# MAX14870_Backend.net
KiCad netlist of a schematic drawn in Altium Designer
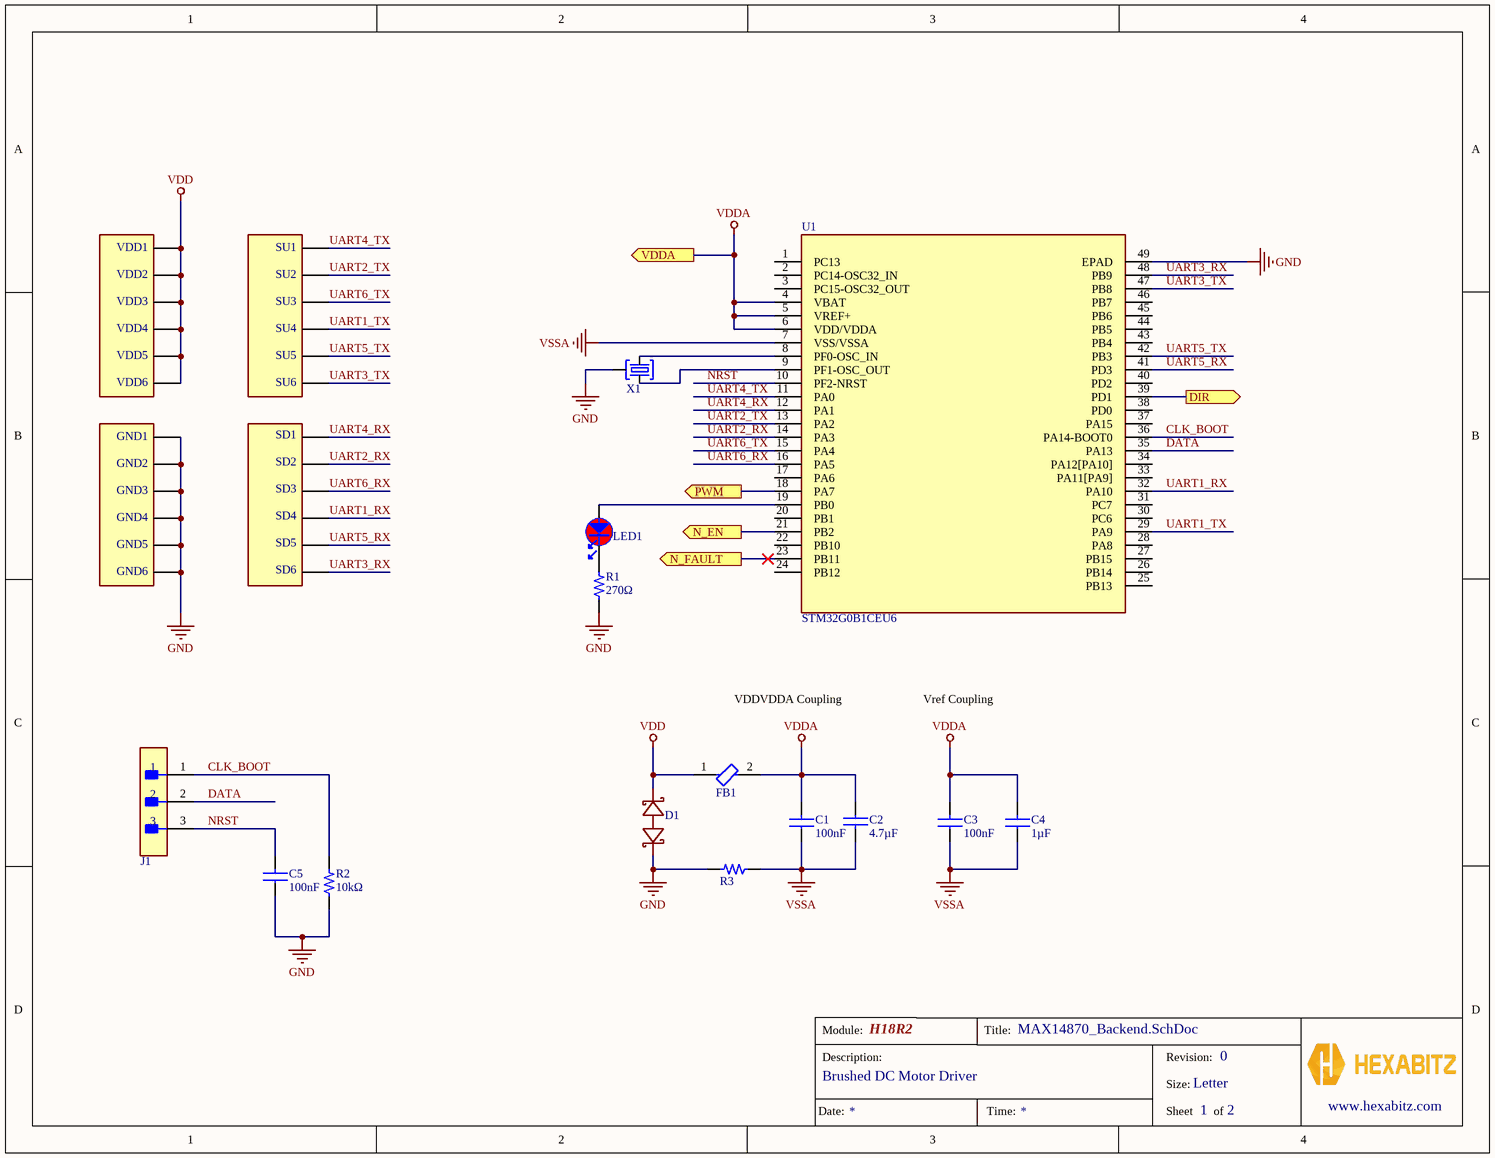
[diagram p0: MAX14870_Backend.SchDoc]

(export (version "E")
  (design (tool "Eeschema 10.0.6"))
  (components
    (comp (ref "C1")
      (value "100nF")
      (footprint "C0603")
      (fields
        (field (name "MANUFACTURER") "Samsung Electro-Mechanics")
        (field (name "MANUFACTURER PART NUMBER") "CL10B104KA8NNNC")
        (field (name "TOLERANCE") "10%")
      )
      (libsource (lib "Hexabitz Altium Library") (part "generic Capacitor"))
    )
    (comp (ref "C2")
      (value "4.7µF")
      (footprint "C0805")
      (fields
        (field (name "MANUFACTURER") "Samsung Electro-Mechanics")
        (field (name "MANUFACTURER PART NUMBER") "CL21X475KAQNNNE")
        (field (name "TOLERANCE") "10%")
      )
      (libsource (lib "Hexabitz Altium Library") (part "generic Capacitor"))
    )
    (comp (ref "C3")
      (value "100nF")
      (footprint "C0603")
      (fields
        (field (name "MANUFACTURER") "Samsung Electro-Mechanics")
        (field (name "MANUFACTURER PART NUMBER") "CL10B104KA8NNNC")
        (field (name "TOLERANCE") "10%")
      )
      (libsource (lib "Hexabitz Altium Library") (part "generic Capacitor"))
    )
    (comp (ref "C4")
      (value "1µF")
      (footprint "C0805")
      (description "Ceramic Capacitor, Ceramic, 16V, 10% +Tol, 10% -Tol, X7R, 15% TC, 1uF, Surface Mount, 0805")
      (fields
        (field (name "MANUFACTURER") "Yageo Group")
        (field (name "MANUFACTURER PART NUMBER") "CC0805KKX7R7BB105")
      )
      (libsource (lib "Hexabitz Altium Library") (part "generic Capacitor"))
    )
    (comp (ref "C5")
      (value "100nF")
      (footprint "C0603")
      (fields
        (field (name "MANUFACTURER") "Samsung Electro-Mechanics")
        (field (name "MANUFACTURER PART NUMBER") "CL10B104KA8NNNC")
        (field (name "TOLERANCE") "10%")
      )
      (libsource (lib "Hexabitz Altium Library") (part "generic Capacitor"))
    )
    (comp (ref "D1")
      (value "CDSOD323-T03SC")
      (footprint "SOD2513X114N")
      (description "A 3V, 350W, bi-directional, standard capacitance, SOD323 pkg TVS Diode ¦ Bourns CDSOD323-T03SC")
      (fields (field (name "MANUFACTURER") "Bourns"))
      (libsource (lib "Hexabitz Altium Library") (part "CDSOD323-T03SC"))
    )
    (comp (ref "FB1")
      (value "MMZ1608Y300B")
      (footprint "FP-MMZ1608-0_8-MFG")
      (description "Ferrite Beads 0603 30ohms 1500mA Signal Line AEC-Q200")
      (fields
        (field (name "MANUFACTURER") "TDK")
        (field (name "MANUFACTURER PART NUMBER") "MMZ1608Y300BTD25")
      )
      (libsource (lib "Hexabitz Altium Library") (part "MMZ1608Y300B"))
    )
    (comp (ref "GND1")
      (value "HEXABIT_UART_PORT")
      (footprint "HEXABIT_POWER_PORT_D")
      (libsource (lib "hexabitz_connectors.Library") (part "HEXABIT_POWER_PORT_D"))
    )
    (comp (ref "GND2")
      (value "HEXABIT_UART_PORT")
      (footprint "HEXABIT_POWER_PORT_D")
      (libsource (lib "hexabitz_connectors.Library") (part "HEXABIT_POWER_PORT_D"))
    )
    (comp (ref "GND3")
      (value "HEXABIT_UART_PORT")
      (footprint "HEXABIT_POWER_PORT_D")
      (libsource (lib "hexabitz_connectors.Library") (part "HEXABIT_POWER_PORT_D"))
    )
    (comp (ref "GND4")
      (value "HEXABIT_UART_PORT")
      (footprint "HEXABIT_POWER_PORT_D")
      (libsource (lib "hexabitz_connectors.Library") (part "HEXABIT_POWER_PORT_D"))
    )
    (comp (ref "GND5")
      (value "HEXABIT_UART_PORT")
      (footprint "HEXABIT_POWER_PORT_D")
      (libsource (lib "hexabitz_connectors.Library") (part "HEXABIT_POWER_PORT_D"))
    )
    (comp (ref "GND6")
      (value "HEXABIT_UART_PORT")
      (footprint "HEXABIT_POWER_PORT_D")
      (libsource (lib "hexabitz_connectors.Library") (part "HEXABIT_POWER_PORT_D"))
    )
    (comp (ref "J1")
      (value "TSW-103-14-G-S")
      (footprint "FP-TSW-103-14-G-S-MFG")
      (description "CONN HEADER VERT 3POS 2.54MM")
      (libsource (lib "Altium Content Vault") (part "cd3439d6ef35ae5d9b27ec4fdd3e828"))
    )
    (comp (ref "LED1")
      (value "VLMS1300-GS08")
      (footprint "FP-6_541-5092_01-4-MFG")
      (description "LED Uni-Color Super Red 639nm 2-Pin Chip 0603(1608Metric) T/R")
      (fields (field (name "MANUFACTURER") "Vishay Semiconductors"))
      (libsource (lib "Hexabitz Altium Library") (part "VLMS1300-GS08"))
    )
    (comp (ref "R1")
      (value "270Ω")
      (footprint "R0603")
      (description "Res Thick Film 0603 270 Ohm 5% 0.1W(1/10W) ±200ppm/C Pad SMD Automotive T/R")
      (fields
        (field (name "MANUFACTURER") "Panasonic")
        (field (name "MANUFACTURER PART NUMBER") "ERJ-3GEYJ271V")
      )
      (libsource (lib "Hexabitz Altium Library") (part "generic Resistor"))
    )
    (comp (ref "R2")
      (value "10kΩ")
      (footprint "R0603")
      (description "100mW Thick Film Resistors ±100ppm/℃ ±1% 10kΩ 0603 Chip Resistor - Surface Mount ROHS")
      (fields
        (field (name "MANUFACTURER") "Yageo Group")
        (field (name "MANUFACTURER PART NUMBER") "RC0603FR-0710KL")
      )
      (libsource (lib "") (part "generic Resistor_1"))
    )
    (comp (ref "R3")
      (value "Manufacturer Part Number")
      (footprint "R0603")
      (libsource (lib "") (part "generic Resistor_2"))
    )
    (comp (ref "SD1")
      (value "HEXABIT_UART_PORT")
      (footprint "HEXABIT_UART_PORT_D")
      (libsource (lib "hexabitz_connectors.Library") (part "HEXABIT_UART_PORT_D"))
    )
    (comp (ref "SD2")
      (value "HEXABIT_UART_PORT")
      (footprint "HEXABIT_UART_PORT_D")
      (libsource (lib "hexabitz_connectors.Library") (part "HEXABIT_UART_PORT_D"))
    )
    (comp (ref "SD3")
      (value "HEXABIT_UART_PORT")
      (footprint "HEXABIT_UART_PORT_D")
      (libsource (lib "hexabitz_connectors.Library") (part "HEXABIT_UART_PORT_D"))
    )
    (comp (ref "SD4")
      (value "HEXABIT_UART_PORT")
      (footprint "HEXABIT_UART_PORT_D")
      (libsource (lib "hexabitz_connectors.Library") (part "HEXABIT_UART_PORT_D"))
    )
    (comp (ref "SD5")
      (value "HEXABIT_UART_PORT")
      (footprint "HEXABIT_UART_PORT_D")
      (libsource (lib "hexabitz_connectors.Library") (part "HEXABIT_UART_PORT_D"))
    )
    (comp (ref "SD6")
      (value "HEXABIT_UART_PORT")
      (footprint "HEXABIT_UART_PORT_D")
      (libsource (lib "hexabitz_connectors.Library") (part "HEXABIT_UART_PORT_D"))
    )
    (comp (ref "SU1")
      (value "HEXABIT_UART_PORT")
      (footprint "HEXABIT_UART_PORT_U")
      (libsource (lib "hexabitz_connectors.Library") (part "HEXABIT_UART_PORT_U"))
    )
    (comp (ref "SU2")
      (value "HEXABIT_UART_PORT")
      (footprint "HEXABIT_UART_PORT_U")
      (libsource (lib "hexabitz_connectors.Library") (part "HEXABIT_UART_PORT_U"))
    )
    (comp (ref "SU3")
      (value "HEXABIT_UART_PORT")
      (footprint "HEXABIT_UART_PORT_U")
      (libsource (lib "hexabitz_connectors.Library") (part "HEXABIT_UART_PORT_U"))
    )
    (comp (ref "SU4")
      (value "HEXABIT_UART_PORT")
      (footprint "HEXABIT_UART_PORT_U")
      (libsource (lib "hexabitz_connectors.Library") (part "HEXABIT_UART_PORT_U"))
    )
    (comp (ref "SU5")
      (value "HEXABIT_UART_PORT")
      (footprint "HEXABIT_UART_PORT_U")
      (libsource (lib "hexabitz_connectors.Library") (part "HEXABIT_UART_PORT_U"))
    )
    (comp (ref "SU6")
      (value "HEXABIT_UART_PORT")
      (footprint "HEXABIT_UART_PORT_U")
      (libsource (lib "hexabitz_connectors.Library") (part "HEXABIT_UART_PORT_U"))
    )
    (comp (ref "U1")
      (value "STM32G0B1CEU6")
      (footprint "QFN50P700X700X65-49N-D")
      (description "MCU 32-bit ARM Cortex M0+ RISC 512KB Flash 1.8V/2.5V/3.3V 48-Pin UFQFPN EP Tray")
      (fields
        (field (name "MANUFACTURER") "STMicroelectronics")
        (field (name "MANUFACTURER PART NUMBER") "STM32G0B1CEU6")
      )
      (libsource (lib "Hexabitz Altium Library") (part "STM32G0B1CEU6"))
    )
    (comp (ref "VDD1")
      (value "HEXABIT_UART_PORT")
      (footprint "HEXABIT_POWER_PORT_U")
      (libsource (lib "hexabitz_connectors.Library") (part "HEXABIT_POWER_PORT_U"))
    )
    (comp (ref "VDD2")
      (value "HEXABIT_UART_PORT")
      (footprint "HEXABIT_POWER_PORT_U")
      (libsource (lib "hexabitz_connectors.Library") (part "HEXABIT_POWER_PORT_U"))
    )
    (comp (ref "VDD3")
      (value "HEXABIT_UART_PORT")
      (footprint "HEXABIT_POWER_PORT_U")
      (libsource (lib "hexabitz_connectors.Library") (part "HEXABIT_POWER_PORT_U"))
    )
    (comp (ref "VDD4")
      (value "HEXABIT_UART_PORT")
      (footprint "HEXABIT_POWER_PORT_U")
      (libsource (lib "hexabitz_connectors.Library") (part "HEXABIT_POWER_PORT_U"))
    )
    (comp (ref "VDD5")
      (value "HEXABIT_UART_PORT")
      (footprint "HEXABIT_POWER_PORT_U")
      (libsource (lib "hexabitz_connectors.Library") (part "HEXABIT_POWER_PORT_U"))
    )
    (comp (ref "VDD6")
      (value "HEXABIT_UART_PORT")
      (footprint "HEXABIT_POWER_PORT_U")
      (libsource (lib "hexabitz_connectors.Library") (part "HEXABIT_POWER_PORT_U"))
    )
    (comp (ref "X1")
      (value "CSTCE8M00G52Z-R0")
      (footprint "XTALL_CSTCE8M00G52")
      (description "Ceramic Resonator 8MHz ±0.5% (Tol) ±0.2% (Stability) 10pF 40Ohm 3-Pin CSMD T/R")
      (fields (field (name "MANUFACTURER") "Murata") (field (name "TOLERANCE") "0.5%"))
      (libsource (lib "Hexabitz Altium Library") (part "CSTCE8M00G52Z-R0"))
    )
  )
  (nets
    (net (code "1") (name "/CLK_BOOT") (class "Default")
      (node (ref "J1") (pin "1") (pinfunction "1_1") (pintype "passive"))
      (node (ref "R2") (pin "1") (pinfunction "1_1") (pintype "passive"))
      (node (ref "U1") (pin "36") (pinfunction "PA14-BOOT0_36") (pintype "passive"))
    )
    (net (code "2") (name "/DATA") (class "Default")
      (node (ref "J1") (pin "2") (pinfunction "2_2") (pintype "passive"))
      (node (ref "U1") (pin "35") (pinfunction "PA13_35") (pintype "passive"))
    )
    (net (code "3") (name "/DIR") (class "Default")
      (node (ref "U1") (pin "39") (pinfunction "PD1_39") (pintype "passive"))
    )
    (net (code "4") (name "/NRST") (class "Default")
      (node (ref "C5") (pin "2") (pinfunction "2_2") (pintype "passive"))
      (node (ref "J1") (pin "3") (pinfunction "3_3") (pintype "passive"))
      (node (ref "U1") (pin "10") (pinfunction "PF2-NRST_10") (pintype "passive"))
    )
    (net (code "5") (name "/N_EN") (class "Default")
      (node (ref "U1") (pin "21") (pinfunction "PB2_21") (pintype "passive"))
    )
    (net (code "6") (name "/N_FAULT") (class "Default")
      (node (ref "U1") (pin "23") (pinfunction "PB11_23") (pintype "passive"))
    )
    (net (code "7") (name "/PWM") (class "Default")
      (node (ref "U1") (pin "18") (pinfunction "PA7_18") (pintype "passive"))
    )
    (net (code "8") (name "/UART1_RX") (class "Default")
      (node (ref "SD4") (pin "UART_D") (pinfunction "UART_D_UART_D") (pintype "passive"))
      (node (ref "U1") (pin "32") (pinfunction "PA10_32") (pintype "passive"))
    )
    (net (code "9") (name "/UART1_TX") (class "Default")
      (node (ref "SU4") (pin "UART_U") (pinfunction "UART_U_UART_U") (pintype "passive"))
      (node (ref "U1") (pin "29") (pinfunction "PA9_29") (pintype "passive"))
    )
    (net (code "10") (name "/UART2_RX") (class "Default")
      (node (ref "SD2") (pin "UART_D") (pinfunction "UART_D_UART_D") (pintype "passive"))
      (node (ref "U1") (pin "14") (pinfunction "PA3_14") (pintype "passive"))
    )
    (net (code "11") (name "/UART2_TX") (class "Default")
      (node (ref "SU2") (pin "UART_U") (pinfunction "UART_U_UART_U") (pintype "passive"))
      (node (ref "U1") (pin "13") (pinfunction "PA2_13") (pintype "passive"))
    )
    (net (code "12") (name "/UART3_RX") (class "Default")
      (node (ref "SD6") (pin "UART_D") (pinfunction "UART_D_UART_D") (pintype "passive"))
      (node (ref "U1") (pin "48") (pinfunction "PB9_48") (pintype "passive"))
    )
    (net (code "13") (name "/UART3_TX") (class "Default")
      (node (ref "SU6") (pin "UART_U") (pinfunction "UART_U_UART_U") (pintype "passive"))
      (node (ref "U1") (pin "47") (pinfunction "PB8_47") (pintype "passive"))
    )
    (net (code "14") (name "/UART4_RX") (class "Default")
      (node (ref "SD1") (pin "UART_D") (pinfunction "UART_D_UART_D") (pintype "passive"))
      (node (ref "U1") (pin "12") (pinfunction "PA1_12") (pintype "passive"))
    )
    (net (code "15") (name "/UART4_TX") (class "Default")
      (node (ref "SU1") (pin "UART_U") (pinfunction "UART_U_UART_U") (pintype "passive"))
      (node (ref "U1") (pin "11") (pinfunction "PA0_11") (pintype "passive"))
    )
    (net (code "16") (name "/UART5_RX") (class "Default")
      (node (ref "SD5") (pin "UART_D") (pinfunction "UART_D_UART_D") (pintype "passive"))
      (node (ref "U1") (pin "41") (pinfunction "PD3_41") (pintype "passive"))
    )
    (net (code "17") (name "/UART5_TX") (class "Default")
      (node (ref "SU5") (pin "UART_U") (pinfunction "UART_U_UART_U") (pintype "passive"))
      (node (ref "U1") (pin "42") (pinfunction "PB3_42") (pintype "passive"))
    )
    (net (code "18") (name "/UART6_RX") (class "Default")
      (node (ref "SD3") (pin "UART_D") (pinfunction "UART_D_UART_D") (pintype "passive"))
      (node (ref "U1") (pin "16") (pinfunction "PA5_16") (pintype "passive"))
    )
    (net (code "19") (name "/UART6_TX") (class "Default")
      (node (ref "SU3") (pin "UART_U") (pinfunction "UART_U_UART_U") (pintype "passive"))
      (node (ref "U1") (pin "15") (pinfunction "PA4_15") (pintype "passive"))
    )
    (net (code "20") (name "GND") (class "Default")
      (node (ref "C5") (pin "1") (pinfunction "1_1") (pintype "passive"))
      (node (ref "D1") (pin "1") (pinfunction "A_1") (pintype "passive"))
      (node (ref "GND1") (pin "Pwr_D") (pinfunction "Pwr_D_Pwr_D") (pintype "passive"))
      (node (ref "GND2") (pin "Pwr_D") (pinfunction "Pwr_D_Pwr_D") (pintype "passive"))
      (node (ref "GND3") (pin "Pwr_D") (pinfunction "Pwr_D_Pwr_D") (pintype "passive"))
      (node (ref "GND4") (pin "Pwr_D") (pinfunction "Pwr_D_Pwr_D") (pintype "passive"))
      (node (ref "GND5") (pin "Pwr_D") (pinfunction "Pwr_D_Pwr_D") (pintype "passive"))
      (node (ref "GND6") (pin "Pwr_D") (pinfunction "Pwr_D_Pwr_D") (pintype "passive"))
      (node (ref "R1") (pin "1") (pinfunction "1_1") (pintype "passive"))
      (node (ref "R2") (pin "2") (pinfunction "2_2") (pintype "passive"))
      (node (ref "R3") (pin "1") (pinfunction "1_1") (pintype "passive"))
      (node (ref "U1") (pin "49") (pinfunction "EPAD_49") (pintype "passive"))
      (node (ref "X1") (pin "P$2") (pinfunction "2_P$2") (pintype "passive"))
    )
    (net (code "21") (name "Net-(LED1-Pad1)") (class "Default")
      (node (ref "LED1") (pin "1") (pintype "passive"))
      (node (ref "R1") (pin "2") (pinfunction "2_2") (pintype "passive"))
    )
    (net (code "22") (name "Net-(U1-PB0)") (class "Default")
      (node (ref "LED1") (pin "2") (pintype "passive"))
      (node (ref "U1") (pin "19") (pinfunction "PB0_19") (pintype "passive"))
    )
    (net (code "23") (name "Net-(U1-PF0-OSC_IN)") (class "Default")
      (node (ref "U1") (pin "8") (pinfunction "PF0-OSC_IN_8") (pintype "passive"))
      (node (ref "X1") (pin "P$3") (pinfunction "3_P$3") (pintype "passive"))
    )
    (net (code "24") (name "Net-(U1-PF1-OSC_OUT)") (class "Default")
      (node (ref "U1") (pin "9") (pinfunction "PF1-OSC_OUT_9") (pintype "passive"))
      (node (ref "X1") (pin "P$1") (pinfunction "1_P$1") (pintype "passive"))
    )
    (net (code "25") (name "VDD") (class "Default")
      (node (ref "D1") (pin "2") (pinfunction "C_2") (pintype "passive"))
      (node (ref "FB1") (pin "1") (pinfunction "1_1") (pintype "passive"))
      (node (ref "VDD1") (pin "Pwr_U") (pinfunction "Pwr_U_Pwr_U") (pintype "passive"))
      (node (ref "VDD2") (pin "Pwr_U") (pinfunction "Pwr_U_Pwr_U") (pintype "passive"))
      (node (ref "VDD3") (pin "Pwr_U") (pinfunction "Pwr_U_Pwr_U") (pintype "passive"))
      (node (ref "VDD4") (pin "Pwr_U") (pinfunction "Pwr_U_Pwr_U") (pintype "passive"))
      (node (ref "VDD5") (pin "Pwr_U") (pinfunction "Pwr_U_Pwr_U") (pintype "passive"))
      (node (ref "VDD6") (pin "Pwr_U") (pinfunction "Pwr_U_Pwr_U") (pintype "passive"))
    )
    (net (code "26") (name "VDDA") (class "Default")
      (node (ref "C1") (pin "2") (pinfunction "2_2") (pintype "passive"))
      (node (ref "C2") (pin "1") (pinfunction "1_1") (pintype "passive"))
      (node (ref "C3") (pin "2") (pinfunction "2_2") (pintype "passive"))
      (node (ref "C4") (pin "2") (pinfunction "2_2") (pintype "passive"))
      (node (ref "FB1") (pin "2") (pinfunction "2_2") (pintype "passive"))
      (node (ref "U1") (pin "4") (pinfunction "VBAT_4") (pintype "passive"))
      (node (ref "U1") (pin "5") (pinfunction "VREF+_5") (pintype "passive"))
      (node (ref "U1") (pin "6") (pinfunction "VDD/VDDA_6") (pintype "passive"))
    )
    (net (code "27") (name "VSSA") (class "Default")
      (node (ref "C1") (pin "1") (pinfunction "1_1") (pintype "passive"))
      (node (ref "C2") (pin "2") (pinfunction "2_2") (pintype "passive"))
      (node (ref "C3") (pin "1") (pinfunction "1_1") (pintype "passive"))
      (node (ref "C4") (pin "1") (pinfunction "1_1") (pintype "passive"))
      (node (ref "R3") (pin "2") (pinfunction "2_2") (pintype "passive"))
      (node (ref "U1") (pin "7") (pinfunction "VSS/VSSA_7") (pintype "passive"))
    )
    (net (code "28") (name "unconnected-(U1-PA6-Pad17)") (class "Default")
      (node (ref "U1") (pin "17") (pinfunction "PA6_17") (pintype "passive"))
    )
    (net (code "29") (name "unconnected-(U1-PA8-Pad28)") (class "Default")
      (node (ref "U1") (pin "28") (pinfunction "PA8_28") (pintype "passive"))
    )
    (net (code "30") (name "unconnected-(U1-PA11[PA9]-Pad33)") (class "Default")
      (node (ref "U1") (pin "33") (pinfunction "PA11[PA9]_33") (pintype "passive"))
    )
    (net (code "31") (name "unconnected-(U1-PA12[PA10]-Pad34)") (class "Default")
      (node (ref "U1") (pin "34") (pinfunction "PA12[PA10]_34") (pintype "passive"))
    )
    (net (code "32") (name "unconnected-(U1-PA15-Pad37)") (class "Default")
      (node (ref "U1") (pin "37") (pinfunction "PA15_37") (pintype "passive"))
    )
    (net (code "33") (name "unconnected-(U1-PB1-Pad20)") (class "Default")
      (node (ref "U1") (pin "20") (pinfunction "PB1_20") (pintype "passive"))
    )
    (net (code "34") (name "unconnected-(U1-PB4-Pad43)") (class "Default")
      (node (ref "U1") (pin "43") (pinfunction "PB4_43") (pintype "passive"))
    )
    (net (code "35") (name "unconnected-(U1-PB5-Pad44)") (class "Default")
      (node (ref "U1") (pin "44") (pinfunction "PB5_44") (pintype "passive"))
    )
    (net (code "36") (name "unconnected-(U1-PB6-Pad45)") (class "Default")
      (node (ref "U1") (pin "45") (pinfunction "PB6_45") (pintype "passive"))
    )
    (net (code "37") (name "unconnected-(U1-PB7-Pad46)") (class "Default")
      (node (ref "U1") (pin "46") (pinfunction "PB7_46") (pintype "passive"))
    )
    (net (code "38") (name "unconnected-(U1-PB10-Pad22)") (class "Default")
      (node (ref "U1") (pin "22") (pinfunction "PB10_22") (pintype "passive"))
    )
    (net (code "39") (name "unconnected-(U1-PB12-Pad24)") (class "Default")
      (node (ref "U1") (pin "24") (pinfunction "PB12_24") (pintype "passive"))
    )
    (net (code "40") (name "unconnected-(U1-PB13-Pad25)") (class "Default")
      (node (ref "U1") (pin "25") (pinfunction "PB13_25") (pintype "passive"))
    )
    (net (code "41") (name "unconnected-(U1-PB14-Pad26)") (class "Default")
      (node (ref "U1") (pin "26") (pinfunction "PB14_26") (pintype "passive"))
    )
    (net (code "42") (name "unconnected-(U1-PB15-Pad27)") (class "Default")
      (node (ref "U1") (pin "27") (pinfunction "PB15_27") (pintype "passive"))
    )
    (net (code "43") (name "unconnected-(U1-PC6-Pad30)") (class "Default")
      (node (ref "U1") (pin "30") (pinfunction "PC6_30") (pintype "passive"))
    )
    (net (code "44") (name "unconnected-(U1-PC7-Pad31)") (class "Default")
      (node (ref "U1") (pin "31") (pinfunction "PC7_31") (pintype "passive"))
    )
    (net (code "45") (name "unconnected-(U1-PC13-Pad1)") (class "Default")
      (node (ref "U1") (pin "1") (pinfunction "PC13_1") (pintype "passive"))
    )
    (net (code "46") (name "unconnected-(U1-PC14-OSC32_IN-Pad2)") (class "Default")
      (node (ref "U1") (pin "2") (pinfunction "PC14-OSC32_IN_2") (pintype "passive"))
    )
    (net (code "47") (name "unconnected-(U1-PC15-OSC32_OUT-Pad3)") (class "Default")
      (node (ref "U1") (pin "3") (pinfunction "PC15-OSC32_OUT_3") (pintype "passive"))
    )
    (net (code "48") (name "unconnected-(U1-PD0-Pad38)") (class "Default")
      (node (ref "U1") (pin "38") (pinfunction "PD0_38") (pintype "passive"))
    )
    (net (code "49") (name "unconnected-(U1-PD2-Pad40)") (class "Default")
      (node (ref "U1") (pin "40") (pinfunction "PD2_40") (pintype "passive"))
    )
  )
)
